# barrieren-a-3.net
KiCad netlist of a schematic drawn in EAGLE
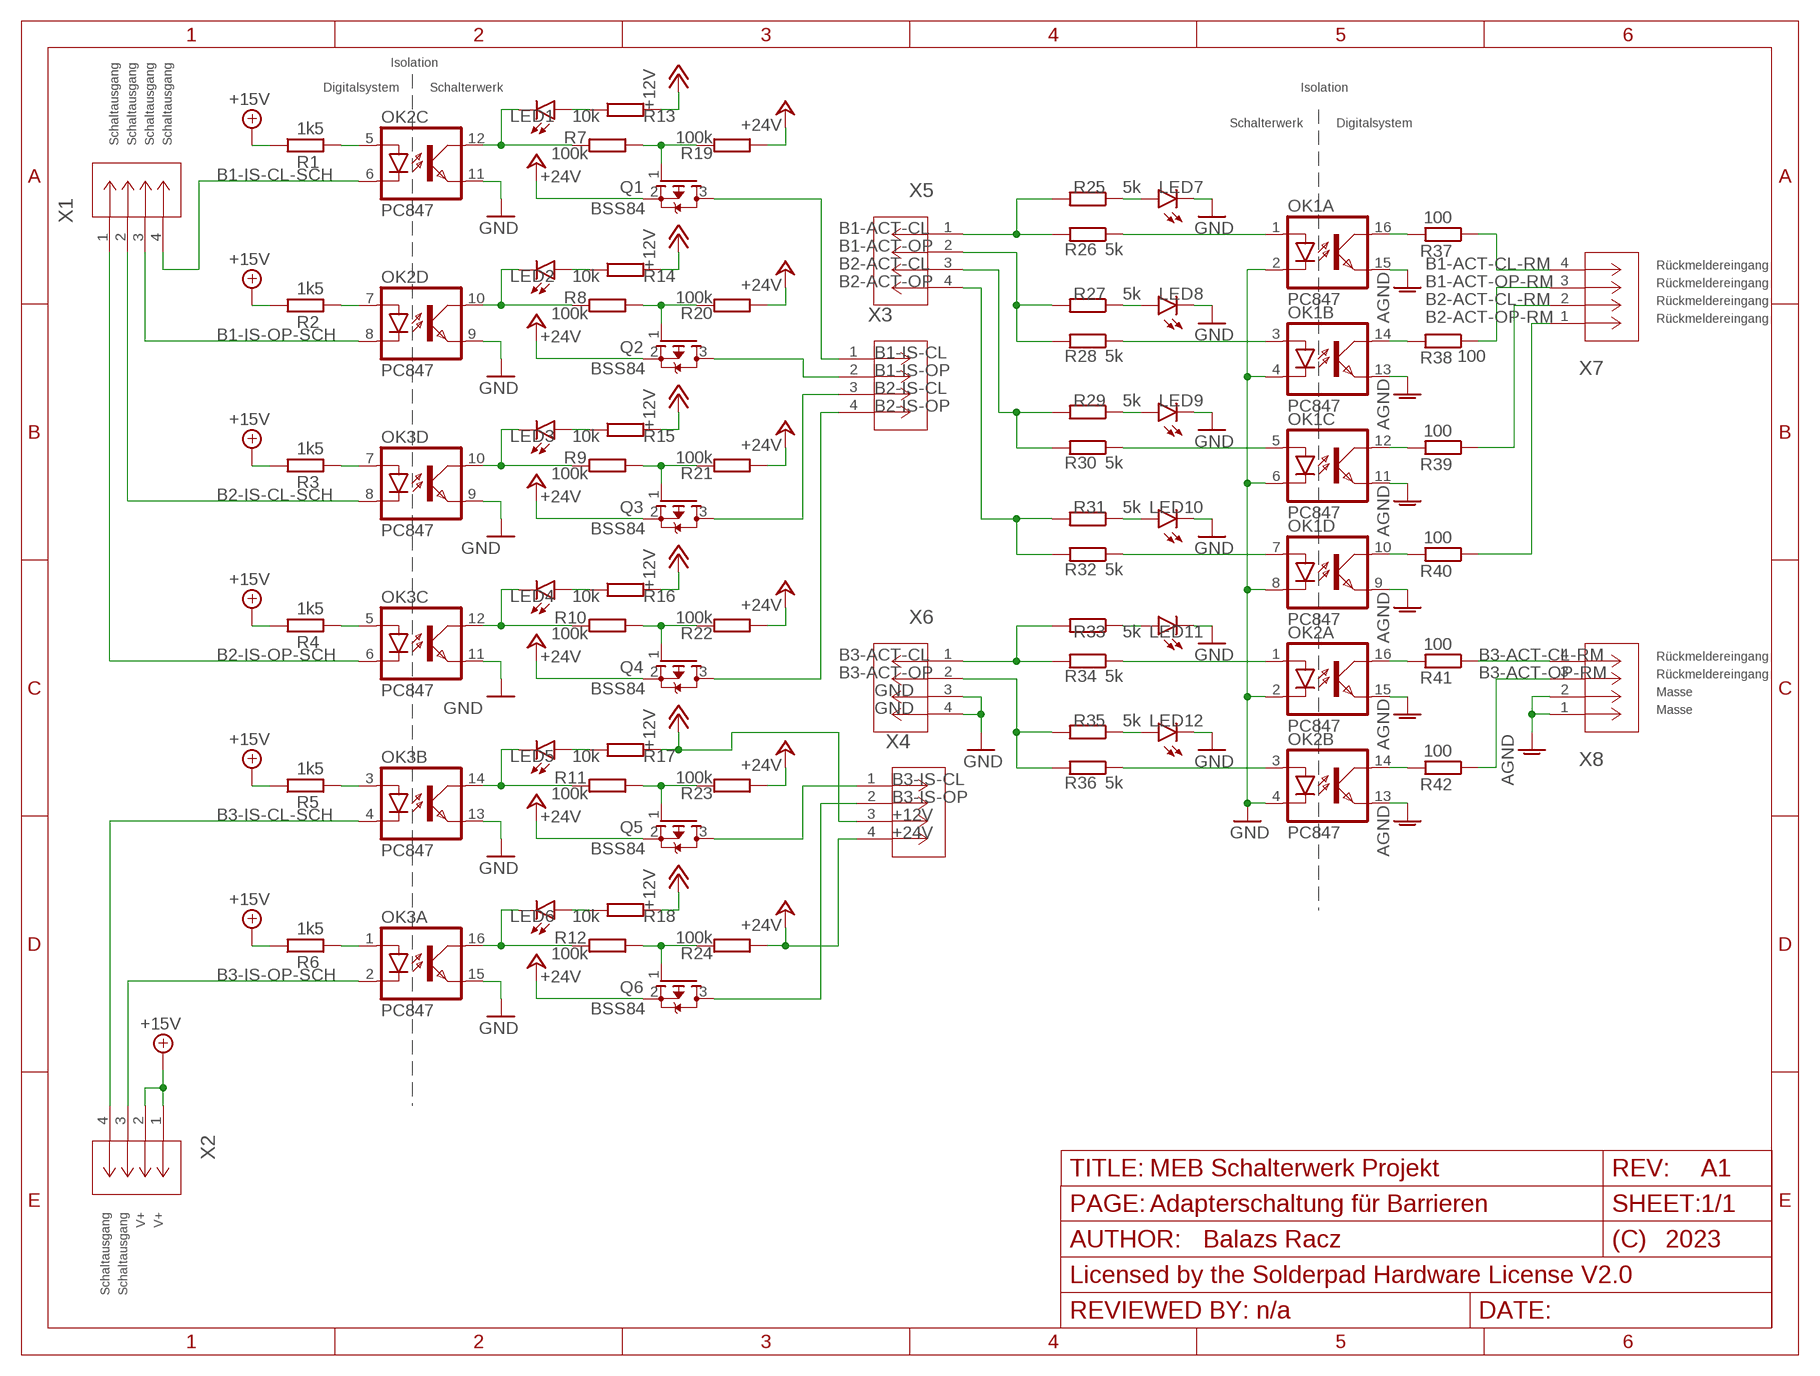
[diagram p0: schematic, sheet 1]

(export (version "E")
  (design (tool "Eeschema 10.0.6"))
  (components
    (comp (ref "LED1")
      (value "LEDCHIPLED_0603")
      (footprint "eagle-import:CHIPLED_0603")
      (libsource (lib "eagle-import") (part "LEDCHIPLED_0603"))
    )
    (comp (ref "LED2")
      (value "LEDCHIPLED_0603")
      (footprint "eagle-import:CHIPLED_0603")
      (libsource (lib "eagle-import") (part "LEDCHIPLED_0603"))
    )
    (comp (ref "LED3")
      (value "LEDCHIPLED_0603")
      (footprint "eagle-import:CHIPLED_0603")
      (libsource (lib "eagle-import") (part "LEDCHIPLED_0603"))
    )
    (comp (ref "LED4")
      (value "LEDCHIPLED_0603")
      (footprint "eagle-import:CHIPLED_0603")
      (libsource (lib "eagle-import") (part "LEDCHIPLED_0603"))
    )
    (comp (ref "LED5")
      (value "LEDCHIPLED_0603")
      (footprint "eagle-import:CHIPLED_0603")
      (libsource (lib "eagle-import") (part "LEDCHIPLED_0603"))
    )
    (comp (ref "LED6")
      (value "LEDCHIPLED_0603")
      (footprint "eagle-import:CHIPLED_0603")
      (libsource (lib "eagle-import") (part "LEDCHIPLED_0603"))
    )
    (comp (ref "LED7")
      (value "LEDCHIPLED_0603")
      (footprint "eagle-import:CHIPLED_0603")
      (libsource (lib "eagle-import") (part "LEDCHIPLED_0603"))
    )
    (comp (ref "LED8")
      (value "LEDCHIPLED_0603")
      (footprint "eagle-import:CHIPLED_0603")
      (libsource (lib "eagle-import") (part "LEDCHIPLED_0603"))
    )
    (comp (ref "LED9")
      (value "LEDCHIPLED_0603")
      (footprint "eagle-import:CHIPLED_0603")
      (libsource (lib "eagle-import") (part "LEDCHIPLED_0603"))
    )
    (comp (ref "LED10")
      (value "LEDCHIPLED_0603")
      (footprint "eagle-import:CHIPLED_0603")
      (libsource (lib "eagle-import") (part "LEDCHIPLED_0603"))
    )
    (comp (ref "LED11")
      (value "LEDCHIPLED_0603")
      (footprint "eagle-import:CHIPLED_0603")
      (libsource (lib "eagle-import") (part "LEDCHIPLED_0603"))
    )
    (comp (ref "LED12")
      (value "LEDCHIPLED_0603")
      (footprint "eagle-import:CHIPLED_0603")
      (libsource (lib "eagle-import") (part "LEDCHIPLED_0603"))
    )
    (comp (ref "OK1")
      (value "PC847")
      (footprint "eagle-import:DIL16")
      (libsource (lib "eagle-import") (part "PC847"))
    )
    (comp (ref "OK2")
      (value "PC847")
      (footprint "eagle-import:DIL16")
      (libsource (lib "eagle-import") (part "PC847"))
    )
    (comp (ref "OK3")
      (value "PC847")
      (footprint "eagle-import:DIL16")
      (libsource (lib "eagle-import") (part "PC847"))
    )
    (comp (ref "Q1")
      (value "BSS84")
      (footprint "eagle-import:SOT23-PCH")
      (libsource (lib "eagle-import") (part "BSS84"))
    )
    (comp (ref "Q2")
      (value "BSS84")
      (footprint "eagle-import:SOT23-PCH")
      (libsource (lib "eagle-import") (part "BSS84"))
    )
    (comp (ref "Q3")
      (value "BSS84")
      (footprint "eagle-import:SOT23-PCH")
      (libsource (lib "eagle-import") (part "BSS84"))
    )
    (comp (ref "Q4")
      (value "BSS84")
      (footprint "eagle-import:SOT23-PCH")
      (libsource (lib "eagle-import") (part "BSS84"))
    )
    (comp (ref "Q5")
      (value "BSS84")
      (footprint "eagle-import:SOT23-PCH")
      (libsource (lib "eagle-import") (part "BSS84"))
    )
    (comp (ref "Q6")
      (value "BSS84")
      (footprint "eagle-import:SOT23-PCH")
      (libsource (lib "eagle-import") (part "BSS84"))
    )
    (comp (ref "R1")
      (value "1k5")
      (footprint "eagle-import:R0805")
      (libsource (lib "eagle-import") (part "R-EU_R0805"))
    )
    (comp (ref "R2")
      (value "1k5")
      (footprint "eagle-import:R0805")
      (libsource (lib "eagle-import") (part "R-EU_R0805"))
    )
    (comp (ref "R3")
      (value "1k5")
      (footprint "eagle-import:R0805")
      (libsource (lib "eagle-import") (part "R-EU_R0805"))
    )
    (comp (ref "R4")
      (value "1k5")
      (footprint "eagle-import:R0805")
      (libsource (lib "eagle-import") (part "R-EU_R0805"))
    )
    (comp (ref "R5")
      (value "1k5")
      (footprint "eagle-import:R0805")
      (libsource (lib "eagle-import") (part "R-EU_R0805"))
    )
    (comp (ref "R6")
      (value "1k5")
      (footprint "eagle-import:R0805")
      (libsource (lib "eagle-import") (part "R-EU_R0805"))
    )
    (comp (ref "R7")
      (value "100k")
      (footprint "eagle-import:R0805")
      (libsource (lib "eagle-import") (part "R-EU_R0805"))
    )
    (comp (ref "R8")
      (value "100k")
      (footprint "eagle-import:R0805")
      (libsource (lib "eagle-import") (part "R-EU_R0805"))
    )
    (comp (ref "R9")
      (value "100k")
      (footprint "eagle-import:R0805")
      (libsource (lib "eagle-import") (part "R-EU_R0805"))
    )
    (comp (ref "R10")
      (value "100k")
      (footprint "eagle-import:R0805")
      (libsource (lib "eagle-import") (part "R-EU_R0805"))
    )
    (comp (ref "R11")
      (value "100k")
      (footprint "eagle-import:R0805")
      (libsource (lib "eagle-import") (part "R-EU_R0805"))
    )
    (comp (ref "R12")
      (value "100k")
      (footprint "eagle-import:R0805")
      (libsource (lib "eagle-import") (part "R-EU_R0805"))
    )
    (comp (ref "R13")
      (value "10k")
      (footprint "eagle-import:R0805")
      (libsource (lib "eagle-import") (part "R-EU_R0805"))
    )
    (comp (ref "R14")
      (value "10k")
      (footprint "eagle-import:R0805")
      (libsource (lib "eagle-import") (part "R-EU_R0805"))
    )
    (comp (ref "R15")
      (value "10k")
      (footprint "eagle-import:R0805")
      (libsource (lib "eagle-import") (part "R-EU_R0805"))
    )
    (comp (ref "R16")
      (value "10k")
      (footprint "eagle-import:R0805")
      (libsource (lib "eagle-import") (part "R-EU_R0805"))
    )
    (comp (ref "R17")
      (value "10k")
      (footprint "eagle-import:R0805")
      (libsource (lib "eagle-import") (part "R-EU_R0805"))
    )
    (comp (ref "R18")
      (value "10k")
      (footprint "eagle-import:R0805")
      (libsource (lib "eagle-import") (part "R-EU_R0805"))
    )
    (comp (ref "R19")
      (value "100k")
      (footprint "eagle-import:R0805")
      (libsource (lib "eagle-import") (part "R-EU_R0805"))
    )
    (comp (ref "R20")
      (value "100k")
      (footprint "eagle-import:R0805")
      (libsource (lib "eagle-import") (part "R-EU_R0805"))
    )
    (comp (ref "R21")
      (value "100k")
      (footprint "eagle-import:R0805")
      (libsource (lib "eagle-import") (part "R-EU_R0805"))
    )
    (comp (ref "R22")
      (value "100k")
      (footprint "eagle-import:R0805")
      (libsource (lib "eagle-import") (part "R-EU_R0805"))
    )
    (comp (ref "R23")
      (value "100k")
      (footprint "eagle-import:R0805")
      (libsource (lib "eagle-import") (part "R-EU_R0805"))
    )
    (comp (ref "R24")
      (value "100k")
      (footprint "eagle-import:R0805")
      (libsource (lib "eagle-import") (part "R-EU_R0805"))
    )
    (comp (ref "R25")
      (value "5k")
      (footprint "eagle-import:R0805")
      (libsource (lib "eagle-import") (part "R-EU_R0805"))
    )
    (comp (ref "R26")
      (value "5k")
      (footprint "eagle-import:R0805")
      (libsource (lib "eagle-import") (part "R-EU_R0805"))
    )
    (comp (ref "R27")
      (value "5k")
      (footprint "eagle-import:R0805")
      (libsource (lib "eagle-import") (part "R-EU_R0805"))
    )
    (comp (ref "R28")
      (value "5k")
      (footprint "eagle-import:R0805")
      (libsource (lib "eagle-import") (part "R-EU_R0805"))
    )
    (comp (ref "R29")
      (value "5k")
      (footprint "eagle-import:R0805")
      (libsource (lib "eagle-import") (part "R-EU_R0805"))
    )
    (comp (ref "R30")
      (value "5k")
      (footprint "eagle-import:R0805")
      (libsource (lib "eagle-import") (part "R-EU_R0805"))
    )
    (comp (ref "R31")
      (value "5k")
      (footprint "eagle-import:R0805")
      (libsource (lib "eagle-import") (part "R-EU_R0805"))
    )
    (comp (ref "R32")
      (value "5k")
      (footprint "eagle-import:R0805")
      (libsource (lib "eagle-import") (part "R-EU_R0805"))
    )
    (comp (ref "R33")
      (value "5k")
      (footprint "eagle-import:R0805")
      (libsource (lib "eagle-import") (part "R-EU_R0805"))
    )
    (comp (ref "R34")
      (value "5k")
      (footprint "eagle-import:R0805")
      (libsource (lib "eagle-import") (part "R-EU_R0805"))
    )
    (comp (ref "R35")
      (value "5k")
      (footprint "eagle-import:R0805")
      (libsource (lib "eagle-import") (part "R-EU_R0805"))
    )
    (comp (ref "R36")
      (value "5k")
      (footprint "eagle-import:R0805")
      (libsource (lib "eagle-import") (part "R-EU_R0805"))
    )
    (comp (ref "R37")
      (value "100")
      (footprint "eagle-import:R0805")
      (libsource (lib "eagle-import") (part "R-EU_R0805"))
    )
    (comp (ref "R38")
      (value "100")
      (footprint "eagle-import:R0805")
      (libsource (lib "eagle-import") (part "R-EU_R0805"))
    )
    (comp (ref "R39")
      (value "100")
      (footprint "eagle-import:R0805")
      (libsource (lib "eagle-import") (part "R-EU_R0805"))
    )
    (comp (ref "R40")
      (value "100")
      (footprint "eagle-import:R0805")
      (libsource (lib "eagle-import") (part "R-EU_R0805"))
    )
    (comp (ref "R41")
      (value "100")
      (footprint "eagle-import:R0805")
      (libsource (lib "eagle-import") (part "R-EU_R0805"))
    )
    (comp (ref "R42")
      (value "100")
      (footprint "eagle-import:R0805")
      (libsource (lib "eagle-import") (part "R-EU_R0805"))
    )
    (comp (ref "X1")
      (value "PHNX_4P_350CONN_1984989_PXC")
      (footprint "eagle-import:PHNX_4P_350")
      (fields
        (field (name "MANUFACTURER_PART_NUMBER") "1984989")
        (field (name "COPYRIGHT") "Copyright (C) 2023 Ultra Librarian. All rights reserved.")
      )
      (libsource (lib "eagle-import") (part "PHNX_4P_350CONN_1984989_PXC"))
    )
    (comp (ref "X2")
      (value "PHNX_4P_350CONN_1984989_PXC")
      (footprint "eagle-import:PHNX_4P_350")
      (fields
        (field (name "MANUFACTURER_PART_NUMBER") "1984989")
        (field (name "COPYRIGHT") "Copyright (C) 2023 Ultra Librarian. All rights reserved.")
      )
      (libsource (lib "eagle-import") (part "PHNX_4P_350CONN_1984989_PXC"))
    )
    (comp (ref "X3")
      (value "PHNX_4P_350CONN_1984989_PXC")
      (footprint "eagle-import:PHNX_4P_350")
      (fields
        (field (name "MANUFACTURER_PART_NUMBER") "1984989")
        (field (name "COPYRIGHT") "Copyright (C) 2023 Ultra Librarian. All rights reserved.")
      )
      (libsource (lib "eagle-import") (part "PHNX_4P_350CONN_1984989_PXC"))
    )
    (comp (ref "X4")
      (value "PHNX_4P_350CONN_1984989_PXC")
      (footprint "eagle-import:PHNX_4P_350")
      (fields
        (field (name "MANUFACTURER_PART_NUMBER") "1984989")
        (field (name "COPYRIGHT") "Copyright (C) 2023 Ultra Librarian. All rights reserved.")
      )
      (libsource (lib "eagle-import") (part "PHNX_4P_350CONN_1984989_PXC"))
    )
    (comp (ref "X5")
      (value "PHNX_4P_350CONN_1984989_PXC")
      (footprint "eagle-import:PHNX_4P_350")
      (fields
        (field (name "MANUFACTURER_PART_NUMBER") "1984989")
        (field (name "COPYRIGHT") "Copyright (C) 2023 Ultra Librarian. All rights reserved.")
      )
      (libsource (lib "eagle-import") (part "PHNX_4P_350CONN_1984989_PXC"))
    )
    (comp (ref "X6")
      (value "PHNX_4P_350CONN_1984989_PXC")
      (footprint "eagle-import:PHNX_4P_350")
      (fields
        (field (name "MANUFACTURER_PART_NUMBER") "1984989")
        (field (name "COPYRIGHT") "Copyright (C) 2023 Ultra Librarian. All rights reserved.")
      )
      (libsource (lib "eagle-import") (part "PHNX_4P_350CONN_1984989_PXC"))
    )
    (comp (ref "X7")
      (value "PHNX_4P_350CONN_1984989_PXC")
      (footprint "eagle-import:PHNX_4P_350")
      (fields
        (field (name "MANUFACTURER_PART_NUMBER") "1984989")
        (field (name "COPYRIGHT") "Copyright (C) 2023 Ultra Librarian. All rights reserved.")
      )
      (libsource (lib "eagle-import") (part "PHNX_4P_350CONN_1984989_PXC"))
    )
    (comp (ref "X8")
      (value "PHNX_4P_350CONN_1984989_PXC")
      (footprint "eagle-import:PHNX_4P_350")
      (fields
        (field (name "MANUFACTURER_PART_NUMBER") "1984989")
        (field (name "COPYRIGHT") "Copyright (C) 2023 Ultra Librarian. All rights reserved.")
      )
      (libsource (lib "eagle-import") (part "PHNX_4P_350CONN_1984989_PXC"))
    )
  )
  (nets
    (net (code "1") (name "+12V") (class "Default")
      (node (ref "R13") (pin "2") (pinfunction "2_2") (pintype "passive"))
      (node (ref "R14") (pin "2") (pinfunction "2_2") (pintype "passive"))
      (node (ref "R15") (pin "2") (pinfunction "2_2") (pintype "passive"))
      (node (ref "R16") (pin "2") (pinfunction "2_2") (pintype "passive"))
      (node (ref "R17") (pin "2") (pinfunction "2_2") (pintype "passive"))
      (node (ref "R18") (pin "2") (pinfunction "2_2") (pintype "passive"))
      (node (ref "X4") (pin "3") (pinfunction "3_3") (pintype "passive"))
    )
    (net (code "2") (name "+15V") (class "Default")
      (node (ref "R1") (pin "1") (pinfunction "1_1") (pintype "passive"))
      (node (ref "R2") (pin "1") (pinfunction "1_1") (pintype "passive"))
      (node (ref "R3") (pin "1") (pinfunction "1_1") (pintype "passive"))
      (node (ref "R4") (pin "1") (pinfunction "1_1") (pintype "passive"))
      (node (ref "R5") (pin "1") (pinfunction "1_1") (pintype "passive"))
      (node (ref "R6") (pin "1") (pinfunction "1_1") (pintype "passive"))
      (node (ref "X2") (pin "1") (pinfunction "1_1") (pintype "passive"))
      (node (ref "X2") (pin "2") (pinfunction "2_2") (pintype "passive"))
    )
    (net (code "3") (name "+24V") (class "Default")
      (node (ref "Q1") (pin "2") (pinfunction "S_2") (pintype "passive"))
      (node (ref "Q2") (pin "2") (pinfunction "S_2") (pintype "passive"))
      (node (ref "Q3") (pin "2") (pinfunction "S_2") (pintype "passive"))
      (node (ref "Q4") (pin "2") (pinfunction "S_2") (pintype "passive"))
      (node (ref "Q5") (pin "2") (pinfunction "S_2") (pintype "passive"))
      (node (ref "Q6") (pin "2") (pinfunction "S_2") (pintype "passive"))
      (node (ref "R19") (pin "2") (pinfunction "2_2") (pintype "passive"))
      (node (ref "R20") (pin "2") (pinfunction "2_2") (pintype "passive"))
      (node (ref "R21") (pin "2") (pinfunction "2_2") (pintype "passive"))
      (node (ref "R22") (pin "2") (pinfunction "2_2") (pintype "passive"))
      (node (ref "R23") (pin "2") (pinfunction "2_2") (pintype "passive"))
      (node (ref "R24") (pin "2") (pinfunction "2_2") (pintype "passive"))
      (node (ref "X4") (pin "4") (pinfunction "4_4") (pintype "passive"))
    )
    (net (code "4") (name "/B1-ACT-CL") (class "Default")
      (node (ref "R25") (pin "2") (pinfunction "2_2") (pintype "passive"))
      (node (ref "R26") (pin "2") (pinfunction "2_2") (pintype "passive"))
      (node (ref "X5") (pin "1") (pinfunction "1_1") (pintype "passive"))
    )
    (net (code "5") (name "/B1-ACT-CL-RM") (class "Default")
      (node (ref "R37") (pin "1") (pinfunction "1_1") (pintype "passive"))
      (node (ref "X7") (pin "4") (pinfunction "4_4") (pintype "passive"))
    )
    (net (code "6") (name "/B1-ACT-OP") (class "Default")
      (node (ref "R27") (pin "2") (pinfunction "2_2") (pintype "passive"))
      (node (ref "R28") (pin "2") (pinfunction "2_2") (pintype "passive"))
      (node (ref "X5") (pin "2") (pinfunction "2_2") (pintype "passive"))
    )
    (net (code "7") (name "/B1-ACT-OP-RM") (class "Default")
      (node (ref "R38") (pin "1") (pinfunction "1_1") (pintype "passive"))
      (node (ref "X7") (pin "3") (pinfunction "3_3") (pintype "passive"))
    )
    (net (code "8") (name "/B1-IS-CL") (class "Default")
      (node (ref "Q1") (pin "3") (pinfunction "D_3") (pintype "passive"))
      (node (ref "X3") (pin "1") (pinfunction "1_1") (pintype "passive"))
    )
    (net (code "9") (name "/B1-IS-CL-SCH") (class "Default")
      (node (ref "OK2") (pin "6") (pinfunction "C_6") (pintype "passive"))
      (node (ref "X1") (pin "4") (pinfunction "4_4") (pintype "passive"))
    )
    (net (code "10") (name "/B1-IS-OP") (class "Default")
      (node (ref "Q2") (pin "3") (pinfunction "D_3") (pintype "passive"))
      (node (ref "X3") (pin "2") (pinfunction "2_2") (pintype "passive"))
    )
    (net (code "11") (name "/B1-IS-OP-SCH") (class "Default")
      (node (ref "OK2") (pin "8") (pinfunction "C_8") (pintype "passive"))
      (node (ref "X1") (pin "3") (pinfunction "3_3") (pintype "passive"))
    )
    (net (code "12") (name "/B2-ACT-CL") (class "Default")
      (node (ref "R29") (pin "2") (pinfunction "2_2") (pintype "passive"))
      (node (ref "R30") (pin "2") (pinfunction "2_2") (pintype "passive"))
      (node (ref "X5") (pin "3") (pinfunction "3_3") (pintype "passive"))
    )
    (net (code "13") (name "/B2-ACT-CL-RM") (class "Default")
      (node (ref "R39") (pin "1") (pinfunction "1_1") (pintype "passive"))
      (node (ref "X7") (pin "2") (pinfunction "2_2") (pintype "passive"))
    )
    (net (code "14") (name "/B2-ACT-OP") (class "Default")
      (node (ref "R31") (pin "2") (pinfunction "2_2") (pintype "passive"))
      (node (ref "R32") (pin "2") (pinfunction "2_2") (pintype "passive"))
      (node (ref "X5") (pin "4") (pinfunction "4_4") (pintype "passive"))
    )
    (net (code "15") (name "/B2-ACT-OP-RM") (class "Default")
      (node (ref "R40") (pin "1") (pinfunction "1_1") (pintype "passive"))
      (node (ref "X7") (pin "1") (pinfunction "1_1") (pintype "passive"))
    )
    (net (code "16") (name "/B2-IS-CL") (class "Default")
      (node (ref "Q3") (pin "3") (pinfunction "D_3") (pintype "passive"))
      (node (ref "X3") (pin "3") (pinfunction "3_3") (pintype "passive"))
    )
    (net (code "17") (name "/B2-IS-CL-SCH") (class "Default")
      (node (ref "OK3") (pin "8") (pinfunction "C_8") (pintype "passive"))
      (node (ref "X1") (pin "2") (pinfunction "2_2") (pintype "passive"))
    )
    (net (code "18") (name "/B2-IS-OP") (class "Default")
      (node (ref "Q4") (pin "3") (pinfunction "D_3") (pintype "passive"))
      (node (ref "X3") (pin "4") (pinfunction "4_4") (pintype "passive"))
    )
    (net (code "19") (name "/B2-IS-OP-SCH") (class "Default")
      (node (ref "OK3") (pin "6") (pinfunction "C_6") (pintype "passive"))
      (node (ref "X1") (pin "1") (pinfunction "1_1") (pintype "passive"))
    )
    (net (code "20") (name "/B3-ACT-CL") (class "Default")
      (node (ref "R33") (pin "2") (pinfunction "2_2") (pintype "passive"))
      (node (ref "R34") (pin "2") (pinfunction "2_2") (pintype "passive"))
      (node (ref "X6") (pin "1") (pinfunction "1_1") (pintype "passive"))
    )
    (net (code "21") (name "/B3-ACT-CL-RM") (class "Default")
      (node (ref "R41") (pin "1") (pinfunction "1_1") (pintype "passive"))
      (node (ref "X8") (pin "4") (pinfunction "4_4") (pintype "passive"))
    )
    (net (code "22") (name "/B3-ACT-OP") (class "Default")
      (node (ref "R35") (pin "2") (pinfunction "2_2") (pintype "passive"))
      (node (ref "R36") (pin "2") (pinfunction "2_2") (pintype "passive"))
      (node (ref "X6") (pin "2") (pinfunction "2_2") (pintype "passive"))
    )
    (net (code "23") (name "/B3-ACT-OP-RM") (class "Default")
      (node (ref "R42") (pin "1") (pinfunction "1_1") (pintype "passive"))
      (node (ref "X8") (pin "3") (pinfunction "3_3") (pintype "passive"))
    )
    (net (code "24") (name "/B3-IS-CL") (class "Default")
      (node (ref "Q5") (pin "3") (pinfunction "D_3") (pintype "passive"))
      (node (ref "X4") (pin "1") (pinfunction "1_1") (pintype "passive"))
    )
    (net (code "25") (name "/B3-IS-CL-SCH") (class "Default")
      (node (ref "OK3") (pin "4") (pinfunction "C_4") (pintype "passive"))
      (node (ref "X2") (pin "4") (pinfunction "4_4") (pintype "passive"))
    )
    (net (code "26") (name "/B3-IS-OP") (class "Default")
      (node (ref "Q6") (pin "3") (pinfunction "D_3") (pintype "passive"))
      (node (ref "X4") (pin "2") (pinfunction "2_2") (pintype "passive"))
    )
    (net (code "27") (name "/B3-IS-OP-SCH") (class "Default")
      (node (ref "OK3") (pin "2") (pinfunction "C_2") (pintype "passive"))
      (node (ref "X2") (pin "3") (pinfunction "3_3") (pintype "passive"))
    )
    (net (code "28") (name "AGND") (class "Default")
      (node (ref "OK1") (pin "11") (pinfunction "EMIT_11") (pintype "passive"))
      (node (ref "OK1") (pin "13") (pinfunction "EMIT_13") (pintype "passive"))
      (node (ref "OK1") (pin "15") (pinfunction "EMIT_15") (pintype "passive"))
      (node (ref "OK1") (pin "9") (pinfunction "EMIT_9") (pintype "passive"))
      (node (ref "OK2") (pin "13") (pinfunction "EMIT_13") (pintype "passive"))
      (node (ref "OK2") (pin "15") (pinfunction "EMIT_15") (pintype "passive"))
      (node (ref "X8") (pin "1") (pinfunction "1_1") (pintype "passive"))
      (node (ref "X8") (pin "2") (pinfunction "2_2") (pintype "passive"))
    )
    (net (code "29") (name "GND") (class "Default")
      (node (ref "LED10") (pin "C") (pinfunction "C_C") (pintype "passive"))
      (node (ref "LED11") (pin "C") (pinfunction "C_C") (pintype "passive"))
      (node (ref "LED12") (pin "C") (pinfunction "C_C") (pintype "passive"))
      (node (ref "LED7") (pin "C") (pinfunction "C_C") (pintype "passive"))
      (node (ref "LED8") (pin "C") (pinfunction "C_C") (pintype "passive"))
      (node (ref "LED9") (pin "C") (pinfunction "C_C") (pintype "passive"))
      (node (ref "OK1") (pin "2") (pinfunction "C_2") (pintype "passive"))
      (node (ref "OK1") (pin "4") (pinfunction "C_4") (pintype "passive"))
      (node (ref "OK1") (pin "6") (pinfunction "C_6") (pintype "passive"))
      (node (ref "OK1") (pin "8") (pinfunction "C_8") (pintype "passive"))
      (node (ref "OK2") (pin "11") (pinfunction "EMIT_11") (pintype "passive"))
      (node (ref "OK2") (pin "2") (pinfunction "C_2") (pintype "passive"))
      (node (ref "OK2") (pin "4") (pinfunction "C_4") (pintype "passive"))
      (node (ref "OK2") (pin "9") (pinfunction "EMIT_9") (pintype "passive"))
      (node (ref "OK3") (pin "11") (pinfunction "EMIT_11") (pintype "passive"))
      (node (ref "OK3") (pin "13") (pinfunction "EMIT_13") (pintype "passive"))
      (node (ref "OK3") (pin "15") (pinfunction "EMIT_15") (pintype "passive"))
      (node (ref "OK3") (pin "9") (pinfunction "EMIT_9") (pintype "passive"))
      (node (ref "X6") (pin "3") (pinfunction "3_3") (pintype "passive"))
      (node (ref "X6") (pin "4") (pinfunction "4_4") (pintype "passive"))
    )
    (net (code "30") (name "Net-(LED1-PadA)") (class "Default")
      (node (ref "LED1") (pin "A") (pinfunction "A_A") (pintype "passive"))
      (node (ref "R13") (pin "1") (pinfunction "1_1") (pintype "passive"))
    )
    (net (code "31") (name "Net-(LED2-PadA)") (class "Default")
      (node (ref "LED2") (pin "A") (pinfunction "A_A") (pintype "passive"))
      (node (ref "R14") (pin "1") (pinfunction "1_1") (pintype "passive"))
    )
    (net (code "32") (name "Net-(LED3-PadA)") (class "Default")
      (node (ref "LED3") (pin "A") (pinfunction "A_A") (pintype "passive"))
      (node (ref "R15") (pin "1") (pinfunction "1_1") (pintype "passive"))
    )
    (net (code "33") (name "Net-(LED4-PadA)") (class "Default")
      (node (ref "LED4") (pin "A") (pinfunction "A_A") (pintype "passive"))
      (node (ref "R16") (pin "1") (pinfunction "1_1") (pintype "passive"))
    )
    (net (code "34") (name "Net-(LED5-PadA)") (class "Default")
      (node (ref "LED5") (pin "A") (pinfunction "A_A") (pintype "passive"))
      (node (ref "R17") (pin "1") (pinfunction "1_1") (pintype "passive"))
    )
    (net (code "35") (name "Net-(LED6-PadA)") (class "Default")
      (node (ref "LED6") (pin "A") (pinfunction "A_A") (pintype "passive"))
      (node (ref "R18") (pin "1") (pinfunction "1_1") (pintype "passive"))
    )
    (net (code "36") (name "Net-(LED7-PadA)") (class "Default")
      (node (ref "LED7") (pin "A") (pinfunction "A_A") (pintype "passive"))
      (node (ref "R25") (pin "1") (pinfunction "1_1") (pintype "passive"))
    )
    (net (code "37") (name "Net-(LED8-PadA)") (class "Default")
      (node (ref "LED8") (pin "A") (pinfunction "A_A") (pintype "passive"))
      (node (ref "R27") (pin "1") (pinfunction "1_1") (pintype "passive"))
    )
    (net (code "38") (name "Net-(LED9-PadA)") (class "Default")
      (node (ref "LED9") (pin "A") (pinfunction "A_A") (pintype "passive"))
      (node (ref "R29") (pin "1") (pinfunction "1_1") (pintype "passive"))
    )
    (net (code "39") (name "Net-(LED10-PadA)") (class "Default")
      (node (ref "LED10") (pin "A") (pinfunction "A_A") (pintype "passive"))
      (node (ref "R31") (pin "1") (pinfunction "1_1") (pintype "passive"))
    )
    (net (code "40") (name "Net-(LED11-PadA)") (class "Default")
      (node (ref "LED11") (pin "A") (pinfunction "A_A") (pintype "passive"))
      (node (ref "R33") (pin "1") (pinfunction "1_1") (pintype "passive"))
    )
    (net (code "41") (name "Net-(LED12-PadA)") (class "Default")
      (node (ref "LED12") (pin "A") (pinfunction "A_A") (pintype "passive"))
      (node (ref "R35") (pin "1") (pinfunction "1_1") (pintype "passive"))
    )
    (net (code "42") (name "Net-(OK1A-A)") (class "Default")
      (node (ref "OK1") (pin "1") (pinfunction "A_1") (pintype "passive"))
      (node (ref "R26") (pin "1") (pinfunction "1_1") (pintype "passive"))
    )
    (net (code "43") (name "Net-(OK1A-COL)") (class "Default")
      (node (ref "OK1") (pin "16") (pinfunction "COL_16") (pintype "passive"))
      (node (ref "R37") (pin "2") (pinfunction "2_2") (pintype "passive"))
    )
    (net (code "44") (name "Net-(OK1B-A)") (class "Default")
      (node (ref "OK1") (pin "3") (pinfunction "A_3") (pintype "passive"))
      (node (ref "R28") (pin "1") (pinfunction "1_1") (pintype "passive"))
    )
    (net (code "45") (name "Net-(OK1B-COL)") (class "Default")
      (node (ref "OK1") (pin "14") (pinfunction "COL_14") (pintype "passive"))
      (node (ref "R38") (pin "2") (pinfunction "2_2") (pintype "passive"))
    )
    (net (code "46") (name "Net-(OK1C-A)") (class "Default")
      (node (ref "OK1") (pin "5") (pinfunction "A_5") (pintype "passive"))
      (node (ref "R30") (pin "1") (pinfunction "1_1") (pintype "passive"))
    )
    (net (code "47") (name "Net-(OK1C-COL)") (class "Default")
      (node (ref "OK1") (pin "12") (pinfunction "COL_12") (pintype "passive"))
      (node (ref "R39") (pin "2") (pinfunction "2_2") (pintype "passive"))
    )
    (net (code "48") (name "Net-(OK1D-A)") (class "Default")
      (node (ref "OK1") (pin "7") (pinfunction "A_7") (pintype "passive"))
      (node (ref "R32") (pin "1") (pinfunction "1_1") (pintype "passive"))
    )
    (net (code "49") (name "Net-(OK1D-COL)") (class "Default")
      (node (ref "OK1") (pin "10") (pinfunction "COL_10") (pintype "passive"))
      (node (ref "R40") (pin "2") (pinfunction "2_2") (pintype "passive"))
    )
    (net (code "50") (name "Net-(OK2A-A)") (class "Default")
      (node (ref "OK2") (pin "1") (pinfunction "A_1") (pintype "passive"))
      (node (ref "R34") (pin "1") (pinfunction "1_1") (pintype "passive"))
    )
    (net (code "51") (name "Net-(OK2A-COL)") (class "Default")
      (node (ref "OK2") (pin "16") (pinfunction "COL_16") (pintype "passive"))
      (node (ref "R41") (pin "2") (pinfunction "2_2") (pintype "passive"))
    )
    (net (code "52") (name "Net-(OK2B-A)") (class "Default")
      (node (ref "OK2") (pin "3") (pinfunction "A_3") (pintype "passive"))
      (node (ref "R36") (pin "1") (pinfunction "1_1") (pintype "passive"))
    )
    (net (code "53") (name "Net-(OK2B-COL)") (class "Default")
      (node (ref "OK2") (pin "14") (pinfunction "COL_14") (pintype "passive"))
      (node (ref "R42") (pin "2") (pinfunction "2_2") (pintype "passive"))
    )
    (net (code "54") (name "Net-(OK2C-A)") (class "Default")
      (node (ref "OK2") (pin "5") (pinfunction "A_5") (pintype "passive"))
      (node (ref "R1") (pin "2") (pinfunction "2_2") (pintype "passive"))
    )
    (net (code "55") (name "Net-(OK2C-COL)") (class "Default")
      (node (ref "LED1") (pin "C") (pinfunction "C_C") (pintype "passive"))
      (node (ref "OK2") (pin "12") (pinfunction "COL_12") (pintype "passive"))
      (node (ref "R7") (pin "2") (pinfunction "2_2") (pintype "passive"))
    )
    (net (code "56") (name "Net-(OK2D-A)") (class "Default")
      (node (ref "OK2") (pin "7") (pinfunction "A_7") (pintype "passive"))
      (node (ref "R2") (pin "2") (pinfunction "2_2") (pintype "passive"))
    )
    (net (code "57") (name "Net-(OK2D-COL)") (class "Default")
      (node (ref "LED2") (pin "C") (pinfunction "C_C") (pintype "passive"))
      (node (ref "OK2") (pin "10") (pinfunction "COL_10") (pintype "passive"))
      (node (ref "R8") (pin "2") (pinfunction "2_2") (pintype "passive"))
    )
    (net (code "58") (name "Net-(OK3A-A)") (class "Default")
      (node (ref "OK3") (pin "1") (pinfunction "A_1") (pintype "passive"))
      (node (ref "R6") (pin "2") (pinfunction "2_2") (pintype "passive"))
    )
    (net (code "59") (name "Net-(OK3A-COL)") (class "Default")
      (node (ref "LED6") (pin "C") (pinfunction "C_C") (pintype "passive"))
      (node (ref "OK3") (pin "16") (pinfunction "COL_16") (pintype "passive"))
      (node (ref "R12") (pin "2") (pinfunction "2_2") (pintype "passive"))
    )
    (net (code "60") (name "Net-(OK3B-A)") (class "Default")
      (node (ref "OK3") (pin "3") (pinfunction "A_3") (pintype "passive"))
      (node (ref "R5") (pin "2") (pinfunction "2_2") (pintype "passive"))
    )
    (net (code "61") (name "Net-(OK3B-COL)") (class "Default")
      (node (ref "LED5") (pin "C") (pinfunction "C_C") (pintype "passive"))
      (node (ref "OK3") (pin "14") (pinfunction "COL_14") (pintype "passive"))
      (node (ref "R11") (pin "2") (pinfunction "2_2") (pintype "passive"))
    )
    (net (code "62") (name "Net-(OK3C-A)") (class "Default")
      (node (ref "OK3") (pin "5") (pinfunction "A_5") (pintype "passive"))
      (node (ref "R4") (pin "2") (pinfunction "2_2") (pintype "passive"))
    )
    (net (code "63") (name "Net-(OK3C-COL)") (class "Default")
      (node (ref "LED4") (pin "C") (pinfunction "C_C") (pintype "passive"))
      (node (ref "OK3") (pin "12") (pinfunction "COL_12") (pintype "passive"))
      (node (ref "R10") (pin "2") (pinfunction "2_2") (pintype "passive"))
    )
    (net (code "64") (name "Net-(OK3D-A)") (class "Default")
      (node (ref "OK3") (pin "7") (pinfunction "A_7") (pintype "passive"))
      (node (ref "R3") (pin "2") (pinfunction "2_2") (pintype "passive"))
    )
    (net (code "65") (name "Net-(OK3D-COL)") (class "Default")
      (node (ref "LED3") (pin "C") (pinfunction "C_C") (pintype "passive"))
      (node (ref "OK3") (pin "10") (pinfunction "COL_10") (pintype "passive"))
      (node (ref "R9") (pin "2") (pinfunction "2_2") (pintype "passive"))
    )
    (net (code "66") (name "Net-(Q1-G)") (class "Default")
      (node (ref "Q1") (pin "1") (pinfunction "G_1") (pintype "passive"))
      (node (ref "R19") (pin "1") (pinfunction "1_1") (pintype "passive"))
      (node (ref "R7") (pin "1") (pinfunction "1_1") (pintype "passive"))
    )
    (net (code "67") (name "Net-(Q2-G)") (class "Default")
      (node (ref "Q2") (pin "1") (pinfunction "G_1") (pintype "passive"))
      (node (ref "R20") (pin "1") (pinfunction "1_1") (pintype "passive"))
      (node (ref "R8") (pin "1") (pinfunction "1_1") (pintype "passive"))
    )
    (net (code "68") (name "Net-(Q3-G)") (class "Default")
      (node (ref "Q3") (pin "1") (pinfunction "G_1") (pintype "passive"))
      (node (ref "R21") (pin "1") (pinfunction "1_1") (pintype "passive"))
      (node (ref "R9") (pin "1") (pinfunction "1_1") (pintype "passive"))
    )
    (net (code "69") (name "Net-(Q4-G)") (class "Default")
      (node (ref "Q4") (pin "1") (pinfunction "G_1") (pintype "passive"))
      (node (ref "R10") (pin "1") (pinfunction "1_1") (pintype "passive"))
      (node (ref "R22") (pin "1") (pinfunction "1_1") (pintype "passive"))
    )
    (net (code "70") (name "Net-(Q5-G)") (class "Default")
      (node (ref "Q5") (pin "1") (pinfunction "G_1") (pintype "passive"))
      (node (ref "R11") (pin "1") (pinfunction "1_1") (pintype "passive"))
      (node (ref "R23") (pin "1") (pinfunction "1_1") (pintype "passive"))
    )
    (net (code "71") (name "Net-(Q6-G)") (class "Default")
      (node (ref "Q6") (pin "1") (pinfunction "G_1") (pintype "passive"))
      (node (ref "R12") (pin "1") (pinfunction "1_1") (pintype "passive"))
      (node (ref "R24") (pin "1") (pinfunction "1_1") (pintype "passive"))
    )
  )
)
